# Placa_Tran.net
KiCad netlist of a schematic drawn in EAGLE
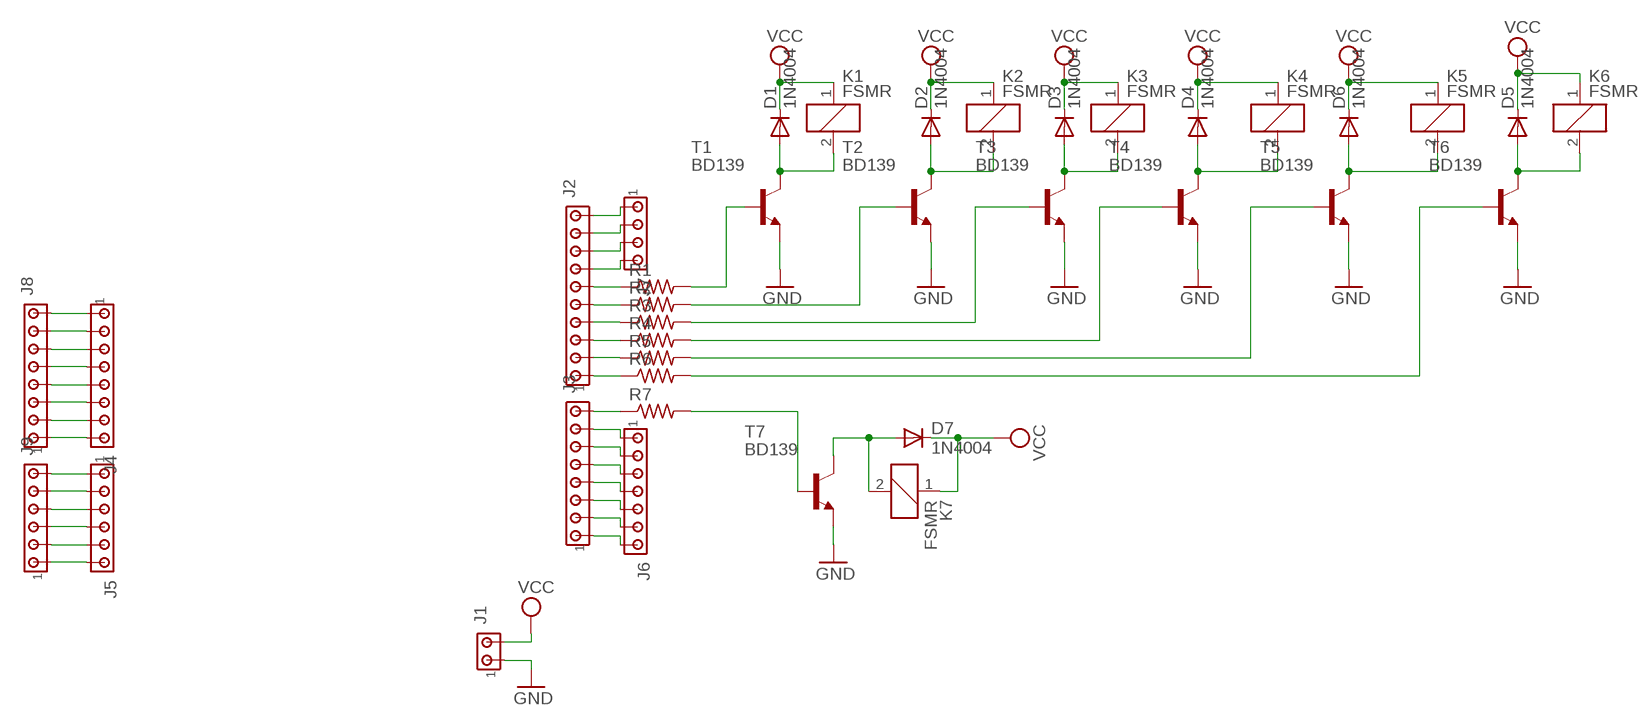
[diagram p0: schematic, sheet 1]

(export (version "E")
  (design (tool "Eeschema 10.0.6"))
  (components
    (comp (ref "D1")
      (value "1N4004")
      (footprint "eagle-import:DO41-10")
      (libsource (lib "eagle-import") (part "1N4004"))
    )
    (comp (ref "D2")
      (value "1N4004")
      (footprint "eagle-import:DO41-10")
      (libsource (lib "eagle-import") (part "1N4004"))
    )
    (comp (ref "D3")
      (value "1N4004")
      (footprint "eagle-import:DO41-10")
      (libsource (lib "eagle-import") (part "1N4004"))
    )
    (comp (ref "D4")
      (value "1N4004")
      (footprint "eagle-import:DO41-10")
      (libsource (lib "eagle-import") (part "1N4004"))
    )
    (comp (ref "D5")
      (value "1N4004")
      (footprint "eagle-import:DO41-10")
      (libsource (lib "eagle-import") (part "1N4004"))
    )
    (comp (ref "D6")
      (value "1N4004")
      (footprint "eagle-import:DO41-10")
      (libsource (lib "eagle-import") (part "1N4004"))
    )
    (comp (ref "D7")
      (value "1N4004")
      (footprint "eagle-import:DO41-10")
      (libsource (lib "eagle-import") (part "1N4004"))
    )
    (comp (ref "J1")
      (value "MTA02-156")
      (footprint "eagle-import:1X2MTA")
      (libsource (lib "eagle-import") (part "MTA02-156"))
    )
    (comp (ref "J2")
      (value "MTA10-100")
      (footprint "eagle-import:10X10MTA")
      (libsource (lib "eagle-import") (part "MTA10-100"))
    )
    (comp (ref "J3")
      (value "MTA08-100")
      (footprint "eagle-import:10X08MTA")
      (libsource (lib "eagle-import") (part "MTA08-100"))
    )
    (comp (ref "J4")
      (value "MTA08-100")
      (footprint "eagle-import:10X08MTA")
      (libsource (lib "eagle-import") (part "MTA08-100"))
    )
    (comp (ref "J5")
      (value "MTA06-100")
      (footprint "eagle-import:10X06MTA")
      (libsource (lib "eagle-import") (part "MTA06-100"))
    )
    (comp (ref "J6")
      (value "MTA07-100")
      (footprint "eagle-import:10X07MTA")
      (libsource (lib "eagle-import") (part "MTA07-100"))
    )
    (comp (ref "J7")
      (value "MTA04-100")
      (footprint "eagle-import:10X04MTA")
      (libsource (lib "eagle-import") (part "MTA04-100"))
    )
    (comp (ref "J8")
      (value "MTA08-100")
      (footprint "eagle-import:10X08MTA")
      (libsource (lib "eagle-import") (part "MTA08-100"))
    )
    (comp (ref "J9")
      (value "MTA06-100")
      (footprint "eagle-import:10X06MTA")
      (libsource (lib "eagle-import") (part "MTA06-100"))
    )
    (comp (ref "K1")
      (value "FSMR")
      (footprint "eagle-import:FSMR")
      (libsource (lib "eagle-import") (part "FSMR"))
    )
    (comp (ref "K2")
      (value "FSMR")
      (footprint "eagle-import:FSMR")
      (libsource (lib "eagle-import") (part "FSMR"))
    )
    (comp (ref "K3")
      (value "FSMR")
      (footprint "eagle-import:FSMR")
      (libsource (lib "eagle-import") (part "FSMR"))
    )
    (comp (ref "K4")
      (value "FSMR")
      (footprint "eagle-import:FSMR")
      (libsource (lib "eagle-import") (part "FSMR"))
    )
    (comp (ref "K5")
      (value "FSMR")
      (footprint "eagle-import:FSMR")
      (libsource (lib "eagle-import") (part "FSMR"))
    )
    (comp (ref "K6")
      (value "FSMR")
      (footprint "eagle-import:FSMR")
      (libsource (lib "eagle-import") (part "FSMR"))
    )
    (comp (ref "K7")
      (value "FSMR")
      (footprint "eagle-import:FSMR")
      (libsource (lib "eagle-import") (part "FSMR"))
    )
    (comp (ref "R1")
      (value "R-US_0207/10")
      (footprint "eagle-import:0207_10")
      (libsource (lib "eagle-import") (part "R-US_0207/10"))
    )
    (comp (ref "R2")
      (value "R-US_0207/10")
      (footprint "eagle-import:0207_10")
      (libsource (lib "eagle-import") (part "R-US_0207/10"))
    )
    (comp (ref "R3")
      (value "R-US_0207/10")
      (footprint "eagle-import:0207_10")
      (libsource (lib "eagle-import") (part "R-US_0207/10"))
    )
    (comp (ref "R4")
      (value "R-US_0207/10")
      (footprint "eagle-import:0207_10")
      (libsource (lib "eagle-import") (part "R-US_0207/10"))
    )
    (comp (ref "R5")
      (value "R-US_0207/10")
      (footprint "eagle-import:0207_10")
      (libsource (lib "eagle-import") (part "R-US_0207/10"))
    )
    (comp (ref "R6")
      (value "R-US_0207/10")
      (footprint "eagle-import:0207_10")
      (libsource (lib "eagle-import") (part "R-US_0207/10"))
    )
    (comp (ref "R7")
      (value "R-US_0207/10")
      (footprint "eagle-import:0207_10")
      (libsource (lib "eagle-import") (part "R-US_0207/10"))
    )
    (comp (ref "T1")
      (value "BD139")
      (footprint "eagle-import:TO126")
      (libsource (lib "eagle-import") (part "BD139"))
    )
    (comp (ref "T2")
      (value "BD139")
      (footprint "eagle-import:TO126")
      (libsource (lib "eagle-import") (part "BD139"))
    )
    (comp (ref "T3")
      (value "BD139")
      (footprint "eagle-import:TO126")
      (libsource (lib "eagle-import") (part "BD139"))
    )
    (comp (ref "T4")
      (value "BD139")
      (footprint "eagle-import:TO126")
      (libsource (lib "eagle-import") (part "BD139"))
    )
    (comp (ref "T5")
      (value "BD139")
      (footprint "eagle-import:TO126")
      (libsource (lib "eagle-import") (part "BD139"))
    )
    (comp (ref "T6")
      (value "BD139")
      (footprint "eagle-import:TO126")
      (libsource (lib "eagle-import") (part "BD139"))
    )
    (comp (ref "T7")
      (value "BD139")
      (footprint "eagle-import:TO126")
      (libsource (lib "eagle-import") (part "BD139"))
    )
  )
  (nets
    (net (code "1") (name "GND") (class "Default")
      (node (ref "J1") (pin "1") (pinfunction "1_1") (pintype "passive"))
      (node (ref "T1") (pin "1") (pinfunction "E_1") (pintype "passive"))
      (node (ref "T2") (pin "1") (pinfunction "E_1") (pintype "passive"))
      (node (ref "T3") (pin "1") (pinfunction "E_1") (pintype "passive"))
      (node (ref "T4") (pin "1") (pinfunction "E_1") (pintype "passive"))
      (node (ref "T5") (pin "1") (pinfunction "E_1") (pintype "passive"))
      (node (ref "T6") (pin "1") (pinfunction "E_1") (pintype "passive"))
      (node (ref "T7") (pin "1") (pinfunction "E_1") (pintype "passive"))
    )
    (net (code "2") (name "Net-(J2-Pad1)") (class "Default")
      (node (ref "J2") (pin "1") (pinfunction "1_1") (pintype "passive"))
      (node (ref "R6") (pin "1") (pinfunction "1_1") (pintype "passive"))
    )
    (net (code "3") (name "Net-(J2-Pad2)") (class "Default")
      (node (ref "J2") (pin "2") (pinfunction "2_2") (pintype "passive"))
      (node (ref "R5") (pin "1") (pinfunction "1_1") (pintype "passive"))
    )
    (net (code "4") (name "Net-(J2-Pad3)") (class "Default")
      (node (ref "J2") (pin "3") (pinfunction "3_3") (pintype "passive"))
      (node (ref "R4") (pin "1") (pinfunction "1_1") (pintype "passive"))
    )
    (net (code "5") (name "Net-(J2-Pad4)") (class "Default")
      (node (ref "J2") (pin "4") (pinfunction "4_4") (pintype "passive"))
      (node (ref "R3") (pin "1") (pinfunction "1_1") (pintype "passive"))
    )
    (net (code "6") (name "Net-(J2-Pad5)") (class "Default")
      (node (ref "J2") (pin "5") (pinfunction "5_5") (pintype "passive"))
      (node (ref "R2") (pin "1") (pinfunction "1_1") (pintype "passive"))
    )
    (net (code "7") (name "Net-(J2-Pad6)") (class "Default")
      (node (ref "J2") (pin "6") (pinfunction "6_6") (pintype "passive"))
      (node (ref "R1") (pin "1") (pinfunction "1_1") (pintype "passive"))
    )
    (net (code "8") (name "Net-(J2-Pad7)") (class "Default")
      (node (ref "J2") (pin "7") (pinfunction "7_7") (pintype "passive"))
      (node (ref "J7") (pin "4") (pinfunction "4_4") (pintype "passive"))
    )
    (net (code "9") (name "Net-(J2-Pad8)") (class "Default")
      (node (ref "J2") (pin "8") (pinfunction "8_8") (pintype "passive"))
      (node (ref "J7") (pin "3") (pinfunction "3_3") (pintype "passive"))
    )
    (net (code "10") (name "Net-(J2-Pad9)") (class "Default")
      (node (ref "J2") (pin "9") (pinfunction "9_9") (pintype "passive"))
      (node (ref "J7") (pin "2") (pinfunction "2_2") (pintype "passive"))
    )
    (net (code "11") (name "Net-(J2-Pad10)") (class "Default")
      (node (ref "J2") (pin "10") (pinfunction "10_10") (pintype "passive"))
      (node (ref "J7") (pin "1") (pinfunction "1_1") (pintype "passive"))
    )
    (net (code "12") (name "Net-(J3-Pad1)") (class "Default")
      (node (ref "J3") (pin "1") (pinfunction "1_1") (pintype "passive"))
      (node (ref "J6") (pin "7") (pinfunction "7_7") (pintype "passive"))
    )
    (net (code "13") (name "Net-(J3-Pad2)") (class "Default")
      (node (ref "J3") (pin "2") (pinfunction "2_2") (pintype "passive"))
      (node (ref "J6") (pin "6") (pinfunction "6_6") (pintype "passive"))
    )
    (net (code "14") (name "Net-(J3-Pad3)") (class "Default")
      (node (ref "J3") (pin "3") (pinfunction "3_3") (pintype "passive"))
      (node (ref "J6") (pin "5") (pinfunction "5_5") (pintype "passive"))
    )
    (net (code "15") (name "Net-(J3-Pad4)") (class "Default")
      (node (ref "J3") (pin "4") (pinfunction "4_4") (pintype "passive"))
      (node (ref "J6") (pin "4") (pinfunction "4_4") (pintype "passive"))
    )
    (net (code "16") (name "Net-(J3-Pad5)") (class "Default")
      (node (ref "J3") (pin "5") (pinfunction "5_5") (pintype "passive"))
      (node (ref "J6") (pin "3") (pinfunction "3_3") (pintype "passive"))
    )
    (net (code "17") (name "Net-(J3-Pad6)") (class "Default")
      (node (ref "J3") (pin "6") (pinfunction "6_6") (pintype "passive"))
      (node (ref "J6") (pin "2") (pinfunction "2_2") (pintype "passive"))
    )
    (net (code "18") (name "Net-(J3-Pad7)") (class "Default")
      (node (ref "J3") (pin "7") (pinfunction "7_7") (pintype "passive"))
      (node (ref "J6") (pin "1") (pinfunction "1_1") (pintype "passive"))
    )
    (net (code "19") (name "Net-(J3-Pad8)") (class "Default")
      (node (ref "J3") (pin "8") (pinfunction "8_8") (pintype "passive"))
      (node (ref "R7") (pin "1") (pinfunction "1_1") (pintype "passive"))
    )
    (net (code "20") (name "Net-(J4-Pad1)") (class "Default")
      (node (ref "J4") (pin "1") (pinfunction "1_1") (pintype "passive"))
      (node (ref "J8") (pin "8") (pinfunction "8_8") (pintype "passive"))
    )
    (net (code "21") (name "Net-(J4-Pad2)") (class "Default")
      (node (ref "J4") (pin "2") (pinfunction "2_2") (pintype "passive"))
      (node (ref "J8") (pin "7") (pinfunction "7_7") (pintype "passive"))
    )
    (net (code "22") (name "Net-(J4-Pad3)") (class "Default")
      (node (ref "J4") (pin "3") (pinfunction "3_3") (pintype "passive"))
      (node (ref "J8") (pin "6") (pinfunction "6_6") (pintype "passive"))
    )
    (net (code "23") (name "Net-(J4-Pad4)") (class "Default")
      (node (ref "J4") (pin "4") (pinfunction "4_4") (pintype "passive"))
      (node (ref "J8") (pin "5") (pinfunction "5_5") (pintype "passive"))
    )
    (net (code "24") (name "Net-(J4-Pad5)") (class "Default")
      (node (ref "J4") (pin "5") (pinfunction "5_5") (pintype "passive"))
      (node (ref "J8") (pin "4") (pinfunction "4_4") (pintype "passive"))
    )
    (net (code "25") (name "Net-(J4-Pad6)") (class "Default")
      (node (ref "J4") (pin "6") (pinfunction "6_6") (pintype "passive"))
      (node (ref "J8") (pin "3") (pinfunction "3_3") (pintype "passive"))
    )
    (net (code "26") (name "Net-(J4-Pad7)") (class "Default")
      (node (ref "J4") (pin "7") (pinfunction "7_7") (pintype "passive"))
      (node (ref "J8") (pin "2") (pinfunction "2_2") (pintype "passive"))
    )
    (net (code "27") (name "Net-(J4-Pad8)") (class "Default")
      (node (ref "J4") (pin "8") (pinfunction "8_8") (pintype "passive"))
      (node (ref "J8") (pin "1") (pinfunction "1_1") (pintype "passive"))
    )
    (net (code "28") (name "Net-(J5-Pad1)") (class "Default")
      (node (ref "J5") (pin "1") (pinfunction "1_1") (pintype "passive"))
      (node (ref "J9") (pin "6") (pinfunction "6_6") (pintype "passive"))
    )
    (net (code "29") (name "Net-(J5-Pad2)") (class "Default")
      (node (ref "J5") (pin "2") (pinfunction "2_2") (pintype "passive"))
      (node (ref "J9") (pin "5") (pinfunction "5_5") (pintype "passive"))
    )
    (net (code "30") (name "Net-(J5-Pad3)") (class "Default")
      (node (ref "J5") (pin "3") (pinfunction "3_3") (pintype "passive"))
      (node (ref "J9") (pin "4") (pinfunction "4_4") (pintype "passive"))
    )
    (net (code "31") (name "Net-(J5-Pad4)") (class "Default")
      (node (ref "J5") (pin "4") (pinfunction "4_4") (pintype "passive"))
      (node (ref "J9") (pin "3") (pinfunction "3_3") (pintype "passive"))
    )
    (net (code "32") (name "Net-(J5-Pad5)") (class "Default")
      (node (ref "J5") (pin "5") (pinfunction "5_5") (pintype "passive"))
      (node (ref "J9") (pin "2") (pinfunction "2_2") (pintype "passive"))
    )
    (net (code "33") (name "Net-(J5-Pad6)") (class "Default")
      (node (ref "J5") (pin "6") (pinfunction "6_6") (pintype "passive"))
      (node (ref "J9") (pin "1") (pinfunction "1_1") (pintype "passive"))
    )
    (net (code "34") (name "Net-(T1-B)") (class "Default")
      (node (ref "R1") (pin "2") (pinfunction "2_2") (pintype "passive"))
      (node (ref "T1") (pin "3") (pinfunction "B_3") (pintype "passive"))
    )
    (net (code "35") (name "Net-(T1-C)") (class "Default")
      (node (ref "D1") (pin "A") (pinfunction "A_A") (pintype "passive"))
      (node (ref "K1") (pin "2") (pinfunction "2_2") (pintype "passive"))
      (node (ref "T1") (pin "2") (pinfunction "C_2") (pintype "passive"))
    )
    (net (code "36") (name "Net-(T2-B)") (class "Default")
      (node (ref "R2") (pin "2") (pinfunction "2_2") (pintype "passive"))
      (node (ref "T2") (pin "3") (pinfunction "B_3") (pintype "passive"))
    )
    (net (code "37") (name "Net-(T2-C)") (class "Default")
      (node (ref "D2") (pin "A") (pinfunction "A_A") (pintype "passive"))
      (node (ref "K2") (pin "2") (pinfunction "2_2") (pintype "passive"))
      (node (ref "T2") (pin "2") (pinfunction "C_2") (pintype "passive"))
    )
    (net (code "38") (name "Net-(T3-B)") (class "Default")
      (node (ref "R3") (pin "2") (pinfunction "2_2") (pintype "passive"))
      (node (ref "T3") (pin "3") (pinfunction "B_3") (pintype "passive"))
    )
    (net (code "39") (name "Net-(T3-C)") (class "Default")
      (node (ref "D3") (pin "A") (pinfunction "A_A") (pintype "passive"))
      (node (ref "K3") (pin "2") (pinfunction "2_2") (pintype "passive"))
      (node (ref "T3") (pin "2") (pinfunction "C_2") (pintype "passive"))
    )
    (net (code "40") (name "Net-(T4-B)") (class "Default")
      (node (ref "R4") (pin "2") (pinfunction "2_2") (pintype "passive"))
      (node (ref "T4") (pin "3") (pinfunction "B_3") (pintype "passive"))
    )
    (net (code "41") (name "Net-(T4-C)") (class "Default")
      (node (ref "D4") (pin "A") (pinfunction "A_A") (pintype "passive"))
      (node (ref "K4") (pin "2") (pinfunction "2_2") (pintype "passive"))
      (node (ref "T4") (pin "2") (pinfunction "C_2") (pintype "passive"))
    )
    (net (code "42") (name "Net-(T5-B)") (class "Default")
      (node (ref "R5") (pin "2") (pinfunction "2_2") (pintype "passive"))
      (node (ref "T5") (pin "3") (pinfunction "B_3") (pintype "passive"))
    )
    (net (code "43") (name "Net-(T5-C)") (class "Default")
      (node (ref "D6") (pin "A") (pinfunction "A_A") (pintype "passive"))
      (node (ref "K5") (pin "2") (pinfunction "2_2") (pintype "passive"))
      (node (ref "T5") (pin "2") (pinfunction "C_2") (pintype "passive"))
    )
    (net (code "44") (name "Net-(T6-B)") (class "Default")
      (node (ref "R6") (pin "2") (pinfunction "2_2") (pintype "passive"))
      (node (ref "T6") (pin "3") (pinfunction "B_3") (pintype "passive"))
    )
    (net (code "45") (name "Net-(T6-C)") (class "Default")
      (node (ref "D5") (pin "A") (pinfunction "A_A") (pintype "passive"))
      (node (ref "K6") (pin "2") (pinfunction "2_2") (pintype "passive"))
      (node (ref "T6") (pin "2") (pinfunction "C_2") (pintype "passive"))
    )
    (net (code "46") (name "Net-(T7-B)") (class "Default")
      (node (ref "R7") (pin "2") (pinfunction "2_2") (pintype "passive"))
      (node (ref "T7") (pin "3") (pinfunction "B_3") (pintype "passive"))
    )
    (net (code "47") (name "Net-(T7-C)") (class "Default")
      (node (ref "D7") (pin "A") (pinfunction "A_A") (pintype "passive"))
      (node (ref "K7") (pin "2") (pinfunction "2_2") (pintype "passive"))
      (node (ref "T7") (pin "2") (pinfunction "C_2") (pintype "passive"))
    )
    (net (code "48") (name "VCC") (class "Default")
      (node (ref "D1") (pin "C") (pinfunction "C_C") (pintype "passive"))
      (node (ref "D2") (pin "C") (pinfunction "C_C") (pintype "passive"))
      (node (ref "D3") (pin "C") (pinfunction "C_C") (pintype "passive"))
      (node (ref "D4") (pin "C") (pinfunction "C_C") (pintype "passive"))
      (node (ref "D5") (pin "C") (pinfunction "C_C") (pintype "passive"))
      (node (ref "D6") (pin "C") (pinfunction "C_C") (pintype "passive"))
      (node (ref "D7") (pin "C") (pinfunction "C_C") (pintype "passive"))
      (node (ref "J1") (pin "2") (pinfunction "2_2") (pintype "passive"))
      (node (ref "K1") (pin "1") (pinfunction "1_1") (pintype "passive"))
      (node (ref "K2") (pin "1") (pinfunction "1_1") (pintype "passive"))
      (node (ref "K3") (pin "1") (pinfunction "1_1") (pintype "passive"))
      (node (ref "K4") (pin "1") (pinfunction "1_1") (pintype "passive"))
      (node (ref "K5") (pin "1") (pinfunction "1_1") (pintype "passive"))
      (node (ref "K6") (pin "1") (pinfunction "1_1") (pintype "passive"))
      (node (ref "K7") (pin "1") (pinfunction "1_1") (pintype "passive"))
    )
  )
)
